# transmitter.net
KiCad netlist of a schematic drawn in EAGLE
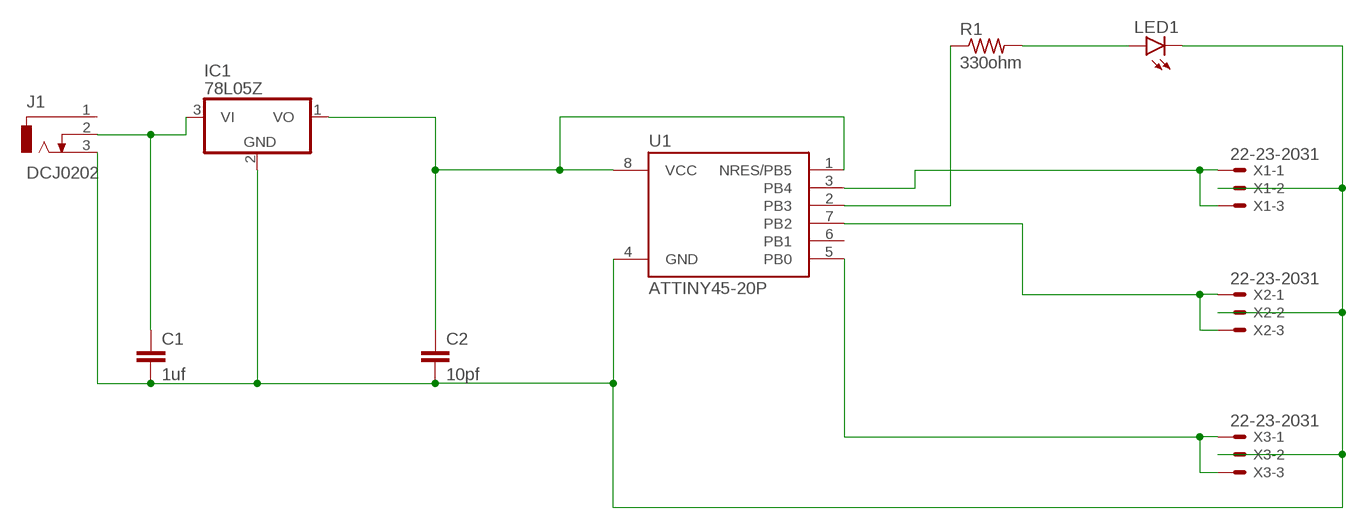
[diagram p0: schematic, sheet 1]

(export (version "E")
  (design (tool "Eeschema 10.0.6"))
  (components
    (comp (ref "C1")
      (value "1uf")
      (footprint "eagle-import:C2.5-2")
      (libsource (lib "eagle-import") (part "C2.5/2"))
    )
    (comp (ref "C2")
      (value "10pf")
      (footprint "eagle-import:C2.5-2")
      (libsource (lib "eagle-import") (part "C2.5/2"))
    )
    (comp (ref "IC1")
      (value "78L05Z")
      (footprint "eagle-import:TO92")
      (libsource (lib "eagle-import") (part "78ZL05"))
    )
    (comp (ref "J1")
      (value "DCJ0202")
      (footprint "eagle-import:DCJ0202")
      (libsource (lib "eagle-import") (part "DCJ0202"))
    )
    (comp (ref "LED1")
      (value "LED3MM")
      (footprint "eagle-import:LED3MM")
      (libsource (lib "eagle-import") (part "LED3MM"))
    )
    (comp (ref "R1")
      (value "330ohm")
      (footprint "eagle-import:0207_10")
      (libsource (lib "eagle-import") (part "R-US_0207/10"))
    )
    (comp (ref "U1")
      (value "ATTINY45-20P")
      (footprint "eagle-import:PDIP08_300MIL")
      (libsource (lib "eagle-import") (part "ATTINY45P-20"))
    )
    (comp (ref "X1")
      (value "22-23-2031")
      (footprint "eagle-import:22-23-2031")
      (fields (field (name "MF") "MOLEX"))
      (libsource (lib "eagle-import") (part "22-23-2031"))
    )
    (comp (ref "X2")
      (value "22-23-2031")
      (footprint "eagle-import:22-23-2031")
      (fields (field (name "MF") "MOLEX"))
      (libsource (lib "eagle-import") (part "22-23-2031"))
    )
    (comp (ref "X3")
      (value "22-23-2031")
      (footprint "eagle-import:22-23-2031")
      (fields (field (name "MF") "MOLEX"))
      (libsource (lib "eagle-import") (part "22-23-2031"))
    )
  )
  (nets
    (net (code "1") (name "Net-(IC1-GND)") (class "Default")
      (node (ref "C1") (pin "2") (pinfunction "2_2") (pintype "passive"))
      (node (ref "C2") (pin "2") (pinfunction "2_2") (pintype "passive"))
      (node (ref "IC1") (pin "2") (pinfunction "GND_2") (pintype "passive"))
      (node (ref "J1") (pin "3") (pinfunction "3_3") (pintype "passive"))
      (node (ref "LED1") (pin "K") (pinfunction "C_K") (pintype "passive"))
      (node (ref "U1") (pin "4") (pinfunction "GND_4") (pintype "power_in"))
      (node (ref "X1") (pin "2") (pinfunction "S_2") (pintype "passive"))
      (node (ref "X2") (pin "2") (pinfunction "S_2") (pintype "passive"))
      (node (ref "X3") (pin "2") (pinfunction "S_2") (pintype "passive"))
    )
    (net (code "2") (name "Net-(IC1-VI)") (class "Default")
      (node (ref "C1") (pin "1") (pinfunction "1_1") (pintype "passive"))
      (node (ref "IC1") (pin "3") (pinfunction "VI_3") (pintype "input"))
      (node (ref "J1") (pin "2") (pinfunction "2_2") (pintype "passive"))
    )
    (net (code "3") (name "Net-(IC1-VO)") (class "Default")
      (node (ref "C2") (pin "1") (pinfunction "1_1") (pintype "passive"))
      (node (ref "IC1") (pin "1") (pinfunction "VO_1") (pintype "passive"))
      (node (ref "U1") (pin "1") (pinfunction "NRES/PB5_1") (pintype "bidirectional"))
      (node (ref "U1") (pin "8") (pinfunction "VCC_8") (pintype "power_in"))
    )
    (net (code "4") (name "Net-(LED1-PadA)") (class "Default")
      (node (ref "LED1") (pin "A") (pinfunction "A_A") (pintype "passive"))
      (node (ref "R1") (pin "2") (pinfunction "2_2") (pintype "passive"))
    )
    (net (code "5") (name "Net-(U1-PB0)") (class "Default")
      (node (ref "U1") (pin "5") (pinfunction "PB0_5") (pintype "bidirectional"))
      (node (ref "X3") (pin "1") (pinfunction "S_1") (pintype "passive"))
      (node (ref "X3") (pin "3") (pinfunction "S_3") (pintype "passive"))
    )
    (net (code "6") (name "Net-(U1-PB2)") (class "Default")
      (node (ref "U1") (pin "7") (pinfunction "PB2_7") (pintype "bidirectional"))
      (node (ref "X2") (pin "1") (pinfunction "S_1") (pintype "passive"))
      (node (ref "X2") (pin "3") (pinfunction "S_3") (pintype "passive"))
    )
    (net (code "7") (name "Net-(U1-PB3)") (class "Default")
      (node (ref "R1") (pin "1") (pinfunction "1_1") (pintype "passive"))
      (node (ref "U1") (pin "2") (pinfunction "PB3_2") (pintype "bidirectional"))
    )
    (net (code "8") (name "Net-(U1-PB4)") (class "Default")
      (node (ref "U1") (pin "3") (pinfunction "PB4_3") (pintype "bidirectional"))
      (node (ref "X1") (pin "1") (pinfunction "S_1") (pintype "passive"))
      (node (ref "X1") (pin "3") (pinfunction "S_3") (pintype "passive"))
    )
    (net (code "9") (name "unconnected-(J1-Pad1)") (class "Default")
      (node (ref "J1") (pin "1") (pinfunction "1_1") (pintype "passive"))
    )
    (net (code "10") (name "unconnected-(U1-PB1-Pad6)") (class "Default")
      (node (ref "U1") (pin "6") (pinfunction "PB1_6") (pintype "bidirectional"))
    )
  )
)
